# motherboard.net
KiCad netlist of a schematic drawn in Altium Designer
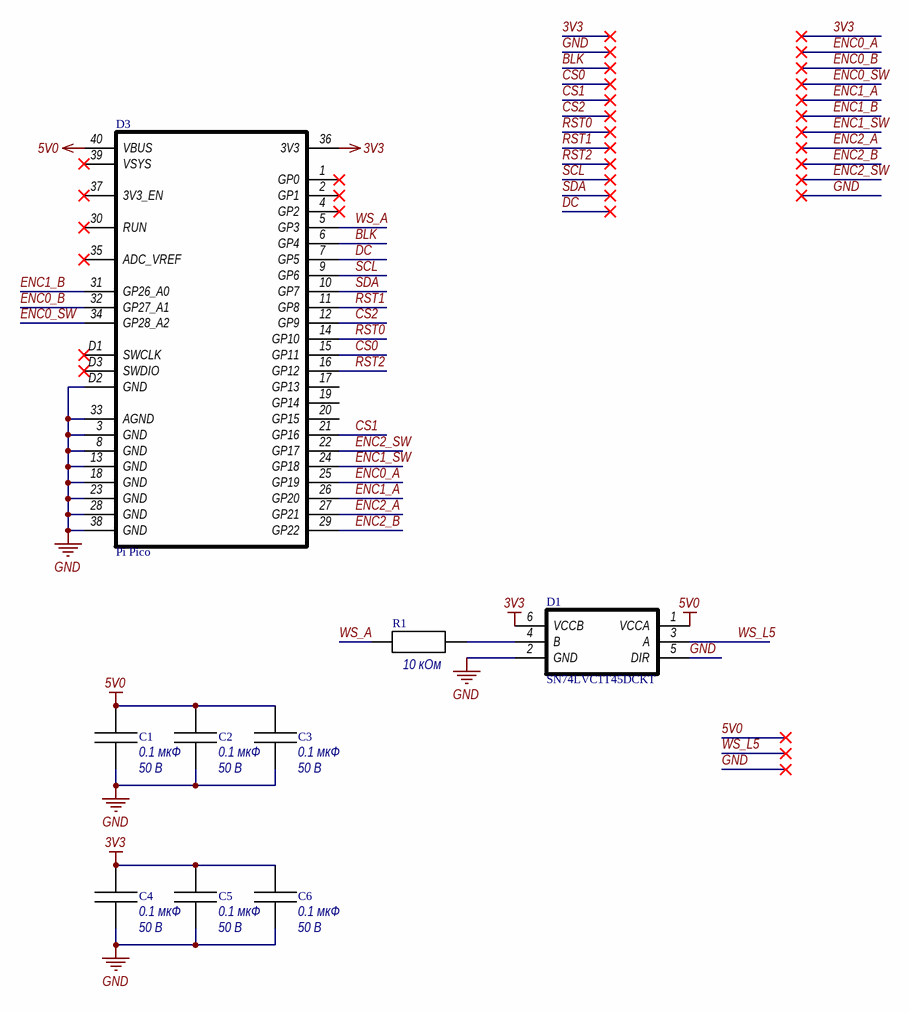
[diagram p0: motherboard.SchDoc]

(export (version "E")
  (design (tool "Eeschema 10.0.6"))
  (components
    (comp (ref "C1")
      (value "0.1 мкФ")
      (footprint "0805-CAP")
      (description "Конденсатор керамический, 0.1 мкФ, X7R, 50 В, точность 10%, 0805")
      (fields (field (name "VOLTAGE") "50 В") (field (name "Comment") "GRM21BR71H104K"))
      (libsource (lib "Altium Vault") (part "Component_1"))
    )
    (comp (ref "C2")
      (value "0.1 мкФ")
      (footprint "0805-CAP")
      (description "Конденсатор керамический, 0.1 мкФ, X7R, 50 В, точность 10%, 0805")
      (fields (field (name "VOLTAGE") "50 В") (field (name "Comment") "GRM21BR71H104K"))
      (libsource (lib "Altium Vault") (part "Component_1"))
    )
    (comp (ref "C3")
      (value "0.1 мкФ")
      (footprint "0805-CAP")
      (description "Конденсатор керамический, 0.1 мкФ, X7R, 50 В, точность 10%, 0805")
      (fields (field (name "VOLTAGE") "50 В") (field (name "Comment") "GRM21BR71H104K"))
      (libsource (lib "Altium Vault") (part "Component_1"))
    )
    (comp (ref "C4")
      (value "0.1 мкФ")
      (footprint "0805-CAP")
      (description "Конденсатор керамический, 0.1 мкФ, X7R, 50 В, точность 10%, 0805")
      (fields (field (name "VOLTAGE") "50 В") (field (name "Comment") "GRM21BR71H104K"))
      (libsource (lib "Altium Vault") (part "Component_1"))
    )
    (comp (ref "C5")
      (value "0.1 мкФ")
      (footprint "0805-CAP")
      (description "Конденсатор керамический, 0.1 мкФ, X7R, 50 В, точность 10%, 0805")
      (fields (field (name "VOLTAGE") "50 В") (field (name "Comment") "GRM21BR71H104K"))
      (libsource (lib "Altium Vault") (part "Component_1"))
    )
    (comp (ref "C6")
      (value "0.1 мкФ")
      (footprint "0805-CAP")
      (description "Конденсатор керамический, 0.1 мкФ, X7R, 50 В, точность 10%, 0805")
      (fields (field (name "VOLTAGE") "50 В") (field (name "Comment") "GRM21BR71H104K"))
      (libsource (lib "Altium Vault") (part "Component_1"))
    )
    (comp (ref "D1")
      (value "SN74LVC1T45DCKT")
      (footprint "sc70-6")
      (description "Преобразователь логических уровней с входом направления, 1.65 - 5.5 В")
      (fields (field (name "MANUFACTURER") "Texas Instruments"))
      (libsource (lib "Altium Vault") (part "CMP-0607-A.1"))
    )
    (comp (ref "D3")
      (value "Pi Pico")
      (footprint "Pi Pico")
      (description "Отладочная плата микроконтроллера RP2040, 1.62 - 3.63 В")
      (fields (field (name "MANUFACTURER") "Raspberry Pi"))
      (libsource (lib "Altium Vault") (part "Pi Pico"))
    )
    (comp (ref "R1")
      (value "10 кОм")
      (footprint "0805-RES")
      (description "Резистор, 10 кОм, 0.125 Вт, точность 1%, 0805")
      (fields (field (name "Comment") "RC0805FR-0710KL"))
      (libsource (lib "") (part "Component_1_1"))
    )
  )
  (nets
    (net (code "1") (name "/BLK") (class "Default")
      (node (ref "D3") (pin "6") (pinfunction "GP4_6") (pintype "passive+no_connect"))
    )
    (net (code "2") (name "/CS0") (class "Default")
      (node (ref "D3") (pin "15") (pinfunction "GP11_15") (pintype "passive+no_connect"))
    )
    (net (code "3") (name "/CS1") (class "Default")
      (node (ref "D3") (pin "21") (pinfunction "GP16_21") (pintype "passive+no_connect"))
    )
    (net (code "4") (name "/CS2") (class "Default")
      (node (ref "D3") (pin "12") (pinfunction "GP9_12") (pintype "passive+no_connect"))
    )
    (net (code "5") (name "/DC") (class "Default")
      (node (ref "D3") (pin "7") (pinfunction "GP5_7") (pintype "passive+no_connect"))
    )
    (net (code "6") (name "/ENC0_A") (class "Default")
      (node (ref "D3") (pin "25") (pinfunction "GP19_25") (pintype "passive+no_connect"))
    )
    (net (code "7") (name "/ENC0_B") (class "Default")
      (node (ref "D3") (pin "32") (pinfunction "GP27_A1_32") (pintype "passive+no_connect"))
    )
    (net (code "8") (name "/ENC0_SW") (class "Default")
      (node (ref "D3") (pin "34") (pinfunction "GP28_A2_34") (pintype "passive+no_connect"))
    )
    (net (code "9") (name "/ENC1_A") (class "Default")
      (node (ref "D3") (pin "26") (pinfunction "GP20_26") (pintype "passive+no_connect"))
    )
    (net (code "10") (name "/ENC1_B") (class "Default")
      (node (ref "D3") (pin "31") (pinfunction "GP26_A0_31") (pintype "passive+no_connect"))
    )
    (net (code "11") (name "/ENC1_SW") (class "Default")
      (node (ref "D3") (pin "24") (pinfunction "GP18_24") (pintype "passive+no_connect"))
    )
    (net (code "12") (name "/ENC2_A") (class "Default")
      (node (ref "D3") (pin "27") (pinfunction "GP21_27") (pintype "passive+no_connect"))
    )
    (net (code "13") (name "/ENC2_B") (class "Default")
      (node (ref "D3") (pin "29") (pinfunction "GP22_29") (pintype "passive+no_connect"))
    )
    (net (code "14") (name "/ENC2_SW") (class "Default")
      (node (ref "D3") (pin "22") (pinfunction "GP17_22") (pintype "passive+no_connect"))
    )
    (net (code "15") (name "/RST0") (class "Default")
      (node (ref "D3") (pin "14") (pinfunction "GP10_14") (pintype "passive+no_connect"))
    )
    (net (code "16") (name "/RST1") (class "Default")
      (node (ref "D3") (pin "11") (pinfunction "GP8_11") (pintype "passive+no_connect"))
    )
    (net (code "17") (name "/RST2") (class "Default")
      (node (ref "D3") (pin "16") (pinfunction "GP12_16") (pintype "passive+no_connect"))
    )
    (net (code "18") (name "/SCL") (class "Default")
      (node (ref "D3") (pin "9") (pinfunction "GP6_9") (pintype "passive+no_connect"))
    )
    (net (code "19") (name "/SDA") (class "Default")
      (node (ref "D3") (pin "10") (pinfunction "GP7_10") (pintype "passive+no_connect"))
    )
    (net (code "20") (name "/WS_A") (class "Default")
      (node (ref "D3") (pin "5") (pinfunction "GP3_5") (pintype "passive"))
      (node (ref "R1") (pin "1") (pinfunction "1_1") (pintype "passive"))
    )
    (net (code "21") (name "/WS_L5") (class "Default")
      (node (ref "D1") (pin "3") (pinfunction "A_3") (pintype "passive+no_connect"))
    )
    (net (code "22") (name "3V3") (class "Default")
      (node (ref "C4") (pin "2") (pinfunction "2_2") (pintype "passive"))
      (node (ref "C5") (pin "2") (pinfunction "2_2") (pintype "passive"))
      (node (ref "C6") (pin "2") (pinfunction "2_2") (pintype "passive"))
      (node (ref "D1") (pin "6") (pinfunction "VCCB_6") (pintype "passive"))
      (node (ref "D3") (pin "36") (pinfunction "3V3_36") (pintype "passive"))
    )
    (net (code "23") (name "5V0") (class "Default")
      (node (ref "C1") (pin "2") (pinfunction "2_2") (pintype "passive"))
      (node (ref "C2") (pin "2") (pinfunction "2_2") (pintype "passive"))
      (node (ref "C3") (pin "2") (pinfunction "2_2") (pintype "passive"))
      (node (ref "D1") (pin "1") (pinfunction "VCCA_1") (pintype "passive"))
      (node (ref "D3") (pin "40") (pinfunction "VBUS_40") (pintype "passive"))
    )
    (net (code "24") (name "GND") (class "Default")
      (node (ref "C1") (pin "1") (pinfunction "1_1") (pintype "passive"))
      (node (ref "C2") (pin "1") (pinfunction "1_1") (pintype "passive"))
      (node (ref "C3") (pin "1") (pinfunction "1_1") (pintype "passive"))
      (node (ref "C4") (pin "1") (pinfunction "1_1") (pintype "passive"))
      (node (ref "C5") (pin "1") (pinfunction "1_1") (pintype "passive"))
      (node (ref "C6") (pin "1") (pinfunction "1_1") (pintype "passive"))
      (node (ref "D1") (pin "2") (pinfunction "GND_2") (pintype "passive"))
      (node (ref "D1") (pin "5") (pinfunction "DIR_5") (pintype "passive"))
      (node (ref "D3") (pin "13") (pinfunction "GND_13") (pintype "passive"))
      (node (ref "D3") (pin "18") (pinfunction "GND_18") (pintype "passive"))
      (node (ref "D3") (pin "23") (pinfunction "GND_23") (pintype "passive"))
      (node (ref "D3") (pin "28") (pinfunction "GND_28") (pintype "passive"))
      (node (ref "D3") (pin "3") (pinfunction "GND_3") (pintype "passive"))
      (node (ref "D3") (pin "33") (pinfunction "AGND_33") (pintype "passive"))
      (node (ref "D3") (pin "38") (pinfunction "GND_38") (pintype "passive"))
      (node (ref "D3") (pin "8") (pinfunction "GND_8") (pintype "passive"))
      (node (ref "D3") (pin "D2") (pinfunction "GND_D2") (pintype "passive"))
    )
    (net (code "25") (name "Net-(D1-B)") (class "Default")
      (node (ref "D1") (pin "4") (pinfunction "B_4") (pintype "passive"))
      (node (ref "R1") (pin "2") (pinfunction "2_2") (pintype "passive"))
    )
    (net (code "26") (name "unconnected-(D3-3V3_EN-Pad37)") (class "Default")
      (node (ref "D3") (pin "37") (pinfunction "3V3_EN_37") (pintype "passive+no_connect"))
    )
    (net (code "27") (name "unconnected-(D3-ADC_VREF-Pad35)") (class "Default")
      (node (ref "D3") (pin "35") (pinfunction "ADC_VREF_35") (pintype "passive+no_connect"))
    )
    (net (code "28") (name "unconnected-(D3-GP0-Pad1)") (class "Default")
      (node (ref "D3") (pin "1") (pinfunction "GP0_1") (pintype "passive+no_connect"))
    )
    (net (code "29") (name "unconnected-(D3-GP1-Pad2)") (class "Default")
      (node (ref "D3") (pin "2") (pinfunction "GP1_2") (pintype "passive+no_connect"))
    )
    (net (code "30") (name "unconnected-(D3-GP2-Pad4)") (class "Default")
      (node (ref "D3") (pin "4") (pinfunction "GP2_4") (pintype "passive+no_connect"))
    )
    (net (code "31") (name "unconnected-(D3-GP13-Pad17)") (class "Default")
      (node (ref "D3") (pin "17") (pinfunction "GP13_17") (pintype "passive"))
    )
    (net (code "32") (name "unconnected-(D3-GP14-Pad19)") (class "Default")
      (node (ref "D3") (pin "19") (pinfunction "GP14_19") (pintype "passive"))
    )
    (net (code "33") (name "unconnected-(D3-GP15-Pad20)") (class "Default")
      (node (ref "D3") (pin "20") (pinfunction "GP15_20") (pintype "passive"))
    )
    (net (code "34") (name "unconnected-(D3-RUN-Pad30)") (class "Default")
      (node (ref "D3") (pin "30") (pinfunction "RUN_30") (pintype "passive+no_connect"))
    )
    (net (code "35") (name "unconnected-(D3-SWCLK-PadD1)") (class "Default")
      (node (ref "D3") (pin "D1") (pinfunction "SWCLK_D1") (pintype "passive+no_connect"))
    )
    (net (code "36") (name "unconnected-(D3-SWDIO-PadD3)") (class "Default")
      (node (ref "D3") (pin "D3") (pinfunction "SWDIO_D3") (pintype "passive+no_connect"))
    )
    (net (code "37") (name "unconnected-(D3-VSYS-Pad39)") (class "Default")
      (node (ref "D3") (pin "39") (pinfunction "VSYS_39") (pintype "passive+no_connect"))
    )
  )
)
